# LMR14050_mod2.net
KiCad netlist of a schematic drawn in Altium Designer
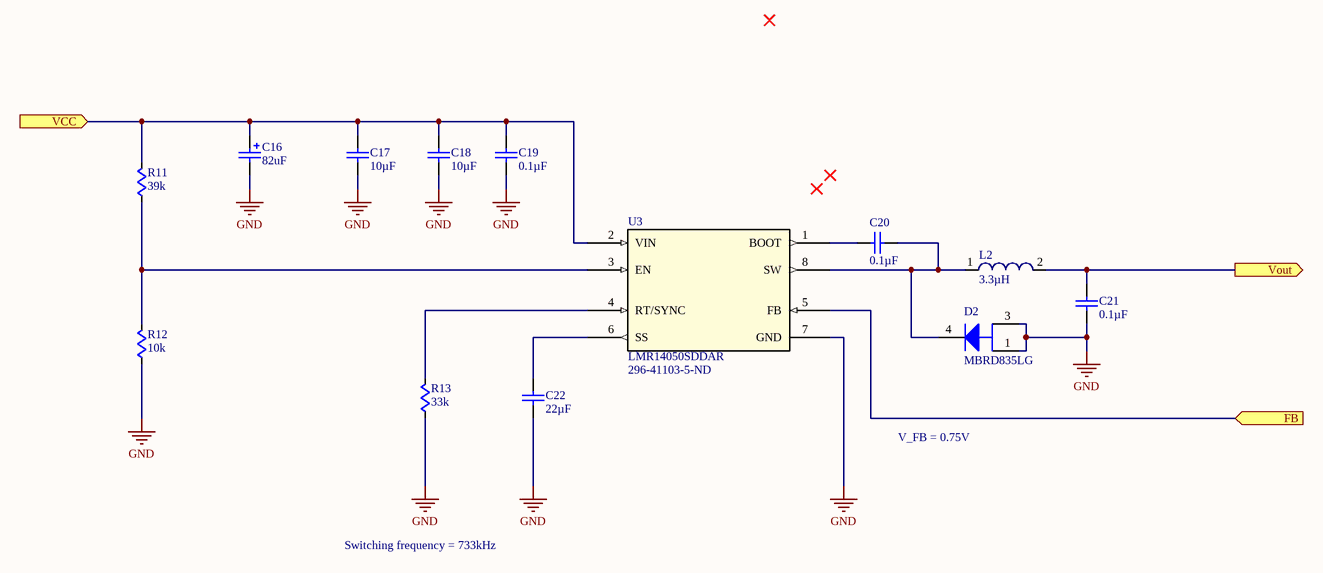
[diagram p0: LMR14050_mod2.SchDoc]

(export (version "E")
  (design (tool "Eeschema 10.0.6"))
  (components
    (comp (ref "C16")
      (value "82uF")
      (footprint "CAP_EEFK_D8")
      (description "Polarized Capacitor (Surface Mount)")
      (fields (field (name "MANUFACTURER_PART_NUMBER") "EEEFK1V680XP"))
      (libsource (lib "AEVC-lib") (part "EEEFK1V680XP"))
    )
    (comp (ref "C17")
      (value "10µF")
      (footprint "C0805")
      (description "capacitor")
      (fields (field (name "Comment") "Cap"))
      (libsource (lib "ChipComponents") (part "Cap"))
    )
    (comp (ref "C18")
      (value "10µF")
      (footprint "C0805")
      (description "capacitor")
      (fields (field (name "Comment") "Cap"))
      (libsource (lib "ChipComponents") (part "Cap"))
    )
    (comp (ref "C19")
      (value "0.1µF")
      (footprint "C0805")
      (description "capacitor")
      (fields (field (name "Comment") "Cap"))
      (libsource (lib "ChipComponents") (part "Cap"))
    )
    (comp (ref "C20")
      (value "0.1µF")
      (footprint "C0805")
      (description "capacitor")
      (fields (field (name "Comment") "Cap"))
      (libsource (lib "ChipComponents") (part "Cap"))
    )
    (comp (ref "C21")
      (value "0.1µF")
      (footprint "C0805")
      (description "capacitor")
      (fields (field (name "Comment") "Cap"))
      (libsource (lib "ChipComponents") (part "Cap"))
    )
    (comp (ref "C22")
      (value "22µF")
      (footprint "C0805")
      (description "capacitor")
      (fields (field (name "Comment") "Cap"))
      (libsource (lib "ChipComponents") (part "Cap"))
    )
    (comp (ref "D2")
      (value "MBRD835LG")
      (footprint "ONSC-DPAK-3-369C-01_V")
      (description "SWITCHMODE(TM) Power Rectifier, 3-Pin DPAK, Pb-Free, Tube")
      (fields (field (name "MANUFACTURER") "On Semiconductor"))
      (libsource (lib "Altium Content Vault") (part "ONSC-D-A1A3K4-3_A"))
    )
    (comp (ref "L2")
      (value "3.3µH")
      (footprint "IHLP-2525C7")
      (description "Inductor")
      (fields (field (name "Comment") "Ind"))
      (libsource (lib "AEVC-bodyBoard") (part "Ind"))
    )
    (comp (ref "R11")
      (value "39k")
      (footprint "R0805")
      (description "resistor")
      (fields (field (name "Comment") "Res"))
      (libsource (lib "ChipComponents") (part "Res"))
    )
    (comp (ref "R12")
      (value "10k")
      (footprint "R0805")
      (description "resistor")
      (fields (field (name "Comment") "Res"))
      (libsource (lib "ChipComponents") (part "Res"))
    )
    (comp (ref "R13")
      (value "33k")
      (footprint "R0805")
      (description "resistor")
      (fields (field (name "Comment") "Res"))
      (libsource (lib "ChipComponents") (part "Res"))
    )
    (comp (ref "U3")
      (value "LMR14050SDDAR")
      (footprint "DDA8")
      (description "dc-dc converter")
      (fields (field (name "SUPPLIER PART NUMBER 1") "296-41103-5-ND"))
      (libsource (lib "AEVC-lib") (part "LMR14050SDDAR"))
    )
  )
  (nets
    (net (code "1") (name "/FB") (class "Default")
      (node (ref "U3") (pin "5") (pinfunction "FB_5") (pintype "input"))
    )
    (net (code "2") (name "/VCC") (class "Default")
      (node (ref "C16") (pin "1") (pinfunction "1_1") (pintype "passive"))
      (node (ref "C17") (pin "2") (pinfunction "2_2") (pintype "passive"))
      (node (ref "C18") (pin "2") (pinfunction "2_2") (pintype "passive"))
      (node (ref "C19") (pin "2") (pinfunction "2_2") (pintype "passive"))
      (node (ref "R11") (pin "2") (pinfunction "2_2") (pintype "passive"))
      (node (ref "U3") (pin "2") (pinfunction "VIN_2") (pintype "input"))
    )
    (net (code "3") (name "/Vout") (class "Default")
      (node (ref "C21") (pin "2") (pinfunction "2_2") (pintype "passive"))
      (node (ref "L2") (pin "2") (pinfunction "2_2") (pintype "passive"))
    )
    (net (code "4") (name "GND") (class "Default")
      (node (ref "C16") (pin "2") (pinfunction "2_2") (pintype "passive"))
      (node (ref "C17") (pin "1") (pinfunction "1_1") (pintype "passive"))
      (node (ref "C18") (pin "1") (pinfunction "1_1") (pintype "passive"))
      (node (ref "C19") (pin "1") (pinfunction "1_1") (pintype "passive"))
      (node (ref "C21") (pin "1") (pinfunction "1_1") (pintype "passive"))
      (node (ref "C22") (pin "1") (pinfunction "1_1") (pintype "passive"))
      (node (ref "D2") (pin "1") (pinfunction "A_1") (pintype "passive"))
      (node (ref "D2") (pin "3") (pinfunction "A_3") (pintype "passive"))
      (node (ref "R12") (pin "1") (pinfunction "1_1") (pintype "passive"))
      (node (ref "R13") (pin "1") (pinfunction "1_1") (pintype "passive"))
      (node (ref "U3") (pin "7") (pinfunction "GND_7") (pintype "power_in"))
    )
    (net (code "5") (name "Net-(D2-K)") (class "Default")
      (node (ref "C20") (pin "1") (pinfunction "1_1") (pintype "passive"))
      (node (ref "D2") (pin "4") (pinfunction "K_4") (pintype "passive"))
      (node (ref "L2") (pin "1") (pinfunction "1_1") (pintype "passive"))
      (node (ref "U3") (pin "8") (pinfunction "SW_8") (pintype "output"))
    )
    (net (code "6") (name "Net-(U3-BOOT)") (class "Default")
      (node (ref "C20") (pin "2") (pinfunction "2_2") (pintype "passive"))
      (node (ref "U3") (pin "1") (pinfunction "BOOT_1") (pintype "output"))
    )
    (net (code "7") (name "Net-(U3-EN)") (class "Default")
      (node (ref "R11") (pin "1") (pinfunction "1_1") (pintype "passive"))
      (node (ref "R12") (pin "2") (pinfunction "2_2") (pintype "passive"))
      (node (ref "U3") (pin "3") (pinfunction "EN_3") (pintype "input"))
    )
    (net (code "8") (name "Net-(U3-RT{slash}SYNC)") (class "Default")
      (node (ref "R13") (pin "2") (pinfunction "2_2") (pintype "passive"))
      (node (ref "U3") (pin "4") (pinfunction "RT/SYNC_4") (pintype "input"))
    )
    (net (code "9") (name "Net-(U3-SS)") (class "Default")
      (node (ref "C22") (pin "2") (pinfunction "2_2") (pintype "passive"))
      (node (ref "U3") (pin "6") (pinfunction "SS_6") (pintype "output"))
    )
  )
)
